# Shematic.net
KiCad netlist of a schematic drawn in Altium Designer
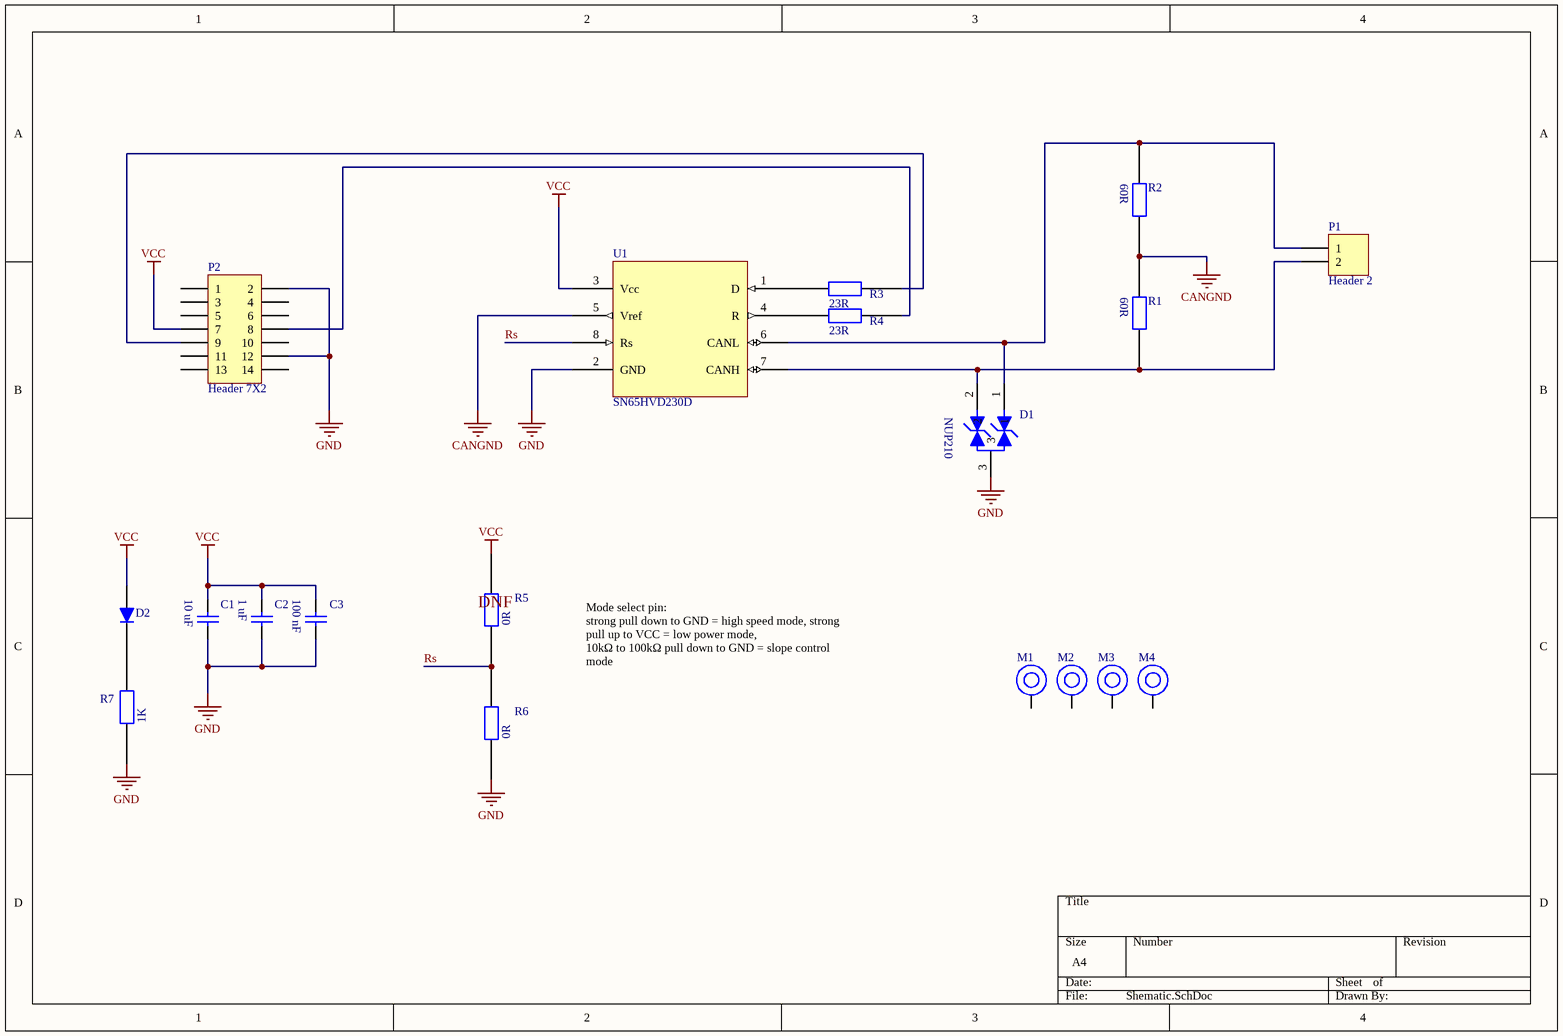
[diagram p0: Shematic.SchDoc]

(export (version "E")
  (design (tool "Eeschema 10.0.6"))
  (components
    (comp (ref "C1")
      (value "GRM21BR61A106KE19L")
      (footprint "CAPC2012")
      (description "Multilayer Ceramic Capacitors MLCC - SMD/SMT 0805 10uF 10volts X5R 10%")
      (fields (field (name "MANUFACTURER") "Murata Electronics") (field (name "TOLERANCE") "10 %"))
      (libsource (lib "Schlib1") (part "GRM21BR61A106KE19L"))
    )
    (comp (ref "C2")
      (value "GCM188R71C105KA64D")
      (footprint "CAPC1608")
      (description "Multilayer Ceramic Capacitors MLCC - SMD/SMT 0603 1.0uF 16volts X7R 10%")
      (fields (field (name "MANUFACTURER") "Murata Electronics") (field (name "TOLERANCE") "10 %"))
      (libsource (lib "Schlib1") (part "GCM188R71C105KA64D"))
    )
    (comp (ref "C3")
      (value "GRJ188R71H104KE11D")
      (footprint "CAPC1608")
      (description "Multilayer Ceramic Capacitors MLCC - SMD/SMT 0603 0.10uF 50volts X7R +/-10% Soft Term")
      (fields (field (name "MANUFACTURER") "Murata Electronics") (field (name "TOLERANCE") "10 %"))
      (libsource (lib "Schlib1") (part "GRJ188R71H104KE11D"))
    )
    (comp (ref "D1")
      (value "SZNUP2105LT3G")
      (footprint "SOT23_A2A1K")
      (description "TVS DIODE 24VWM 44VC SOT23")
      (fields (field (name "MANUFACTURER") "ON Semiconductor"))
      (libsource (lib "Schlib1") (part "SZNUP2105LT3G"))
    )
    (comp (ref "D2")
      (value "LTST-C191KGKT")
      (footprint "LEDC1608M_AK")
      (description "LED GREEN CLEAR 0603 SMD")
      (fields (field (name "MANUFACTURER") "Lite-On Inc."))
      (libsource (lib "Schlib1") (part "LTST-C191KGKT"))
    )
    (comp (ref "M1")
      (value "M")
      (footprint "MOUNTING")
      (description "MOUNTING HOLE - NON INSTALLABLE")
      (libsource (lib "SMD Mechanical") (part "MOUNTING"))
    )
    (comp (ref "M2")
      (value "M")
      (footprint "MOUNTING")
      (description "MOUNTING HOLE - NON INSTALLABLE")
      (libsource (lib "SMD Mechanical") (part "MOUNTING"))
    )
    (comp (ref "M3")
      (value "M")
      (footprint "MOUNTING")
      (description "MOUNTING HOLE - NON INSTALLABLE")
      (libsource (lib "SMD Mechanical") (part "MOUNTING"))
    )
    (comp (ref "M4")
      (value "M")
      (footprint "MOUNTING")
      (description "MOUNTING HOLE - NON INSTALLABLE")
      (libsource (lib "SMD Mechanical") (part "MOUNTING"))
    )
    (comp (ref "P1")
      (value "Header 2")
      (footprint "Custom TH Ver2.1:TERM_BLOCK_2_HORZ_RIACON01")
      (description "Header, 2-Pin")
      (fields (field (name "PUBLISHER") "Altium Limited"))
      (libsource (lib "Miscellaneous Connectors") (part "Header 2"))
    )
    (comp (ref "P2")
      (value "Header 7X2")
      (footprint "IDC14-B")
      (description "Header, 7-Pin, Dual row")
      (fields (field (name "PUBLISHER") "Altium Limited"))
      (libsource (lib "Miscellaneous Connectors") (part "Header 7X2"))
    )
    (comp (ref "R1")
      (value "CR0603-FX-60R4ELF")
      (footprint "RESC1608")
      (description "RES SMD 60.4 OHM 1% 1/10W 0603")
      (fields (field (name "MANUFACTURER") "Bourns Inc.") (field (name "TOLERANCE") "±1%"))
      (libsource (lib "Schlib1") (part "CR0603-FX-60R4ELF"))
    )
    (comp (ref "R2")
      (value "CR0603-FX-60R4ELF")
      (footprint "RESC1608")
      (description "RES SMD 60.4 OHM 1% 1/10W 0603")
      (fields (field (name "MANUFACTURER") "Bourns Inc.") (field (name "TOLERANCE") "±1%"))
      (libsource (lib "Schlib1") (part "CR0603-FX-60R4ELF"))
    )
    (comp (ref "R3")
      (value "CR0603-FX-23R2ELF")
      (footprint "RESC1608")
      (description "RES SMD 23.2 OHM 1% 1/10W 0603")
      (fields (field (name "MANUFACTURER") "Bourns Inc.") (field (name "TOLERANCE") "±1%"))
      (libsource (lib "Schlib1") (part "CR0603-FX-23R2ELF"))
    )
    (comp (ref "R4")
      (value "CR0603-FX-23R2ELF")
      (footprint "RESC1608")
      (description "RES SMD 23.2 OHM 1% 1/10W 0603")
      (fields (field (name "MANUFACTURER") "Bourns Inc.") (field (name "TOLERANCE") "±1%"))
      (libsource (lib "Schlib1") (part "CR0603-FX-23R2ELF"))
    )
    (comp (ref "R5")
      (value "CR0603-J/-000ELF")
      (footprint "RESC1608")
      (description "RES SMD 0.0OHM JUMPER 1/10W 0603")
      (fields (field (name "MANUFACTURER") "Bourns Inc.") (field (name "TOLERANCE") "Jumper"))
      (libsource (lib "Schlib1") (part "CR0603-J/-000ELF"))
    )
    (comp (ref "R6")
      (value "CR0603-J/-000ELF")
      (footprint "RESC1608")
      (description "RES SMD 0.0OHM JUMPER 1/10W 0603")
      (fields (field (name "MANUFACTURER") "Bourns Inc.") (field (name "TOLERANCE") "Jumper"))
      (libsource (lib "Schlib1") (part "CR0603-J/-000ELF"))
    )
    (comp (ref "R7")
      (value "CR0603-FX-1001ELF")
      (footprint "RESC1608")
      (description "RES SMD 1K OHM 1% 1/10W 0603")
      (fields (field (name "MANUFACTURER") "Bourns Inc.") (field (name "TOLERANCE") "±1%"))
      (libsource (lib "Schlib1") (part "CR0603-FX-1001ELF"))
    )
    (comp (ref "U1")
      (value "SN65HVD230D")
      (footprint "SOIC127P580-8N")
      (description "IC CAN TRANSCEIVER 3.3V 8-SOIC")
      (fields (field (name "MANUFACTURER") "Texas Instruments"))
      (libsource (lib "Schlib1") (part "SN65HVD230D"))
    )
  )
  (nets
    (net (code "1") (name "/Rs") (class "Default")
      (node (ref "R5") (pin "1") (pintype "passive"))
      (node (ref "R6") (pin "2") (pintype "passive"))
      (node (ref "U1") (pin "8") (pinfunction "Rs_8") (pintype "input"))
    )
    (net (code "2") (name "CANGND") (class "Default")
      (node (ref "R1") (pin "1") (pintype "passive"))
      (node (ref "R2") (pin "2") (pintype "passive"))
      (node (ref "U1") (pin "5") (pinfunction "Vref_5") (pintype "output"))
    )
    (net (code "3") (name "GND") (class "Default")
      (node (ref "C1") (pin "2") (pinfunction "2_2") (pintype "passive"))
      (node (ref "C2") (pin "2") (pinfunction "2_2") (pintype "passive"))
      (node (ref "C3") (pin "2") (pinfunction "2_2") (pintype "passive"))
      (node (ref "D1") (pin "3") (pinfunction "3_3") (pintype "passive"))
      (node (ref "P2") (pin "12") (pinfunction "12_12") (pintype "passive"))
      (node (ref "P2") (pin "2") (pinfunction "2_2") (pintype "passive"))
      (node (ref "R6") (pin "1") (pintype "passive"))
      (node (ref "R7") (pin "1") (pintype "passive"))
      (node (ref "U1") (pin "2") (pinfunction "GND_2") (pintype "power_in"))
    )
    (net (code "4") (name "Net-(D2-PadK)") (class "Default")
      (node (ref "D2") (pin "K") (pinfunction "K_K") (pintype "passive"))
      (node (ref "R7") (pin "2") (pintype "passive"))
    )
    (net (code "5") (name "Net-(P2-Pad8)") (class "Default")
      (node (ref "P2") (pin "8") (pinfunction "8_8") (pintype "passive"))
      (node (ref "R4") (pin "2") (pintype "passive"))
    )
    (net (code "6") (name "Net-(P2-Pad9)") (class "Default")
      (node (ref "P2") (pin "9") (pinfunction "9_9") (pintype "passive"))
      (node (ref "R3") (pin "2") (pintype "passive"))
    )
    (net (code "7") (name "Net-(U1-CANH)") (class "Default")
      (node (ref "D1") (pin "2") (pinfunction "2_2") (pintype "passive"))
      (node (ref "P1") (pin "2") (pinfunction "2_2") (pintype "passive"))
      (node (ref "R1") (pin "2") (pintype "passive"))
      (node (ref "U1") (pin "7") (pinfunction "CANH_7") (pintype "bidirectional"))
    )
    (net (code "8") (name "Net-(U1-CANL)") (class "Default")
      (node (ref "D1") (pin "1") (pinfunction "1_1") (pintype "passive"))
      (node (ref "P1") (pin "1") (pinfunction "1_1") (pintype "passive"))
      (node (ref "R2") (pin "1") (pintype "passive"))
      (node (ref "U1") (pin "6") (pinfunction "CANL_6") (pintype "bidirectional"))
    )
    (net (code "9") (name "Net-(U1-D)") (class "Default")
      (node (ref "R3") (pin "1") (pintype "passive"))
      (node (ref "U1") (pin "1") (pinfunction "D_1") (pintype "input"))
    )
    (net (code "10") (name "Net-(U1-R)") (class "Default")
      (node (ref "R4") (pin "1") (pintype "passive"))
      (node (ref "U1") (pin "4") (pinfunction "R_4") (pintype "output"))
    )
    (net (code "11") (name "VCC") (class "Default")
      (node (ref "C1") (pin "1") (pinfunction "1_1") (pintype "passive"))
      (node (ref "C2") (pin "1") (pinfunction "1_1") (pintype "passive"))
      (node (ref "C3") (pin "1") (pinfunction "1_1") (pintype "passive"))
      (node (ref "D2") (pin "A") (pinfunction "A_A") (pintype "passive"))
      (node (ref "P2") (pin "7") (pinfunction "7_7") (pintype "passive"))
      (node (ref "R5") (pin "2") (pintype "passive"))
      (node (ref "U1") (pin "3") (pinfunction "Vcc_3") (pintype "power_in"))
    )
    (net (code "12") (name "unconnected-(M1-Pad1)") (class "Default")
      (node (ref "M1") (pin "1") (pinfunction "1_1") (pintype "passive"))
    )
    (net (code "13") (name "unconnected-(M2-Pad1)") (class "Default")
      (node (ref "M2") (pin "1") (pinfunction "1_1") (pintype "passive"))
    )
    (net (code "14") (name "unconnected-(M3-Pad1)") (class "Default")
      (node (ref "M3") (pin "1") (pinfunction "1_1") (pintype "passive"))
    )
    (net (code "15") (name "unconnected-(M4-Pad1)") (class "Default")
      (node (ref "M4") (pin "1") (pinfunction "1_1") (pintype "passive"))
    )
    (net (code "16") (name "unconnected-(P2-Pad1)") (class "Default")
      (node (ref "P2") (pin "1") (pinfunction "1_1") (pintype "passive"))
    )
    (net (code "17") (name "unconnected-(P2-Pad3)") (class "Default")
      (node (ref "P2") (pin "3") (pinfunction "3_3") (pintype "passive"))
    )
    (net (code "18") (name "unconnected-(P2-Pad4)") (class "Default")
      (node (ref "P2") (pin "4") (pinfunction "4_4") (pintype "passive"))
    )
    (net (code "19") (name "unconnected-(P2-Pad5)") (class "Default")
      (node (ref "P2") (pin "5") (pinfunction "5_5") (pintype "passive"))
    )
    (net (code "20") (name "unconnected-(P2-Pad6)") (class "Default")
      (node (ref "P2") (pin "6") (pinfunction "6_6") (pintype "passive"))
    )
    (net (code "21") (name "unconnected-(P2-Pad10)") (class "Default")
      (node (ref "P2") (pin "10") (pinfunction "10_10") (pintype "passive"))
    )
    (net (code "22") (name "unconnected-(P2-Pad11)") (class "Default")
      (node (ref "P2") (pin "11") (pinfunction "11_11") (pintype "passive"))
    )
    (net (code "23") (name "unconnected-(P2-Pad13)") (class "Default")
      (node (ref "P2") (pin "13") (pinfunction "13_13") (pintype "passive"))
    )
    (net (code "24") (name "unconnected-(P2-Pad14)") (class "Default")
      (node (ref "P2") (pin "14") (pinfunction "14_14") (pintype "passive"))
    )
  )
)
